# Power_board.net
KiCad netlist of a schematic drawn in Altium Designer
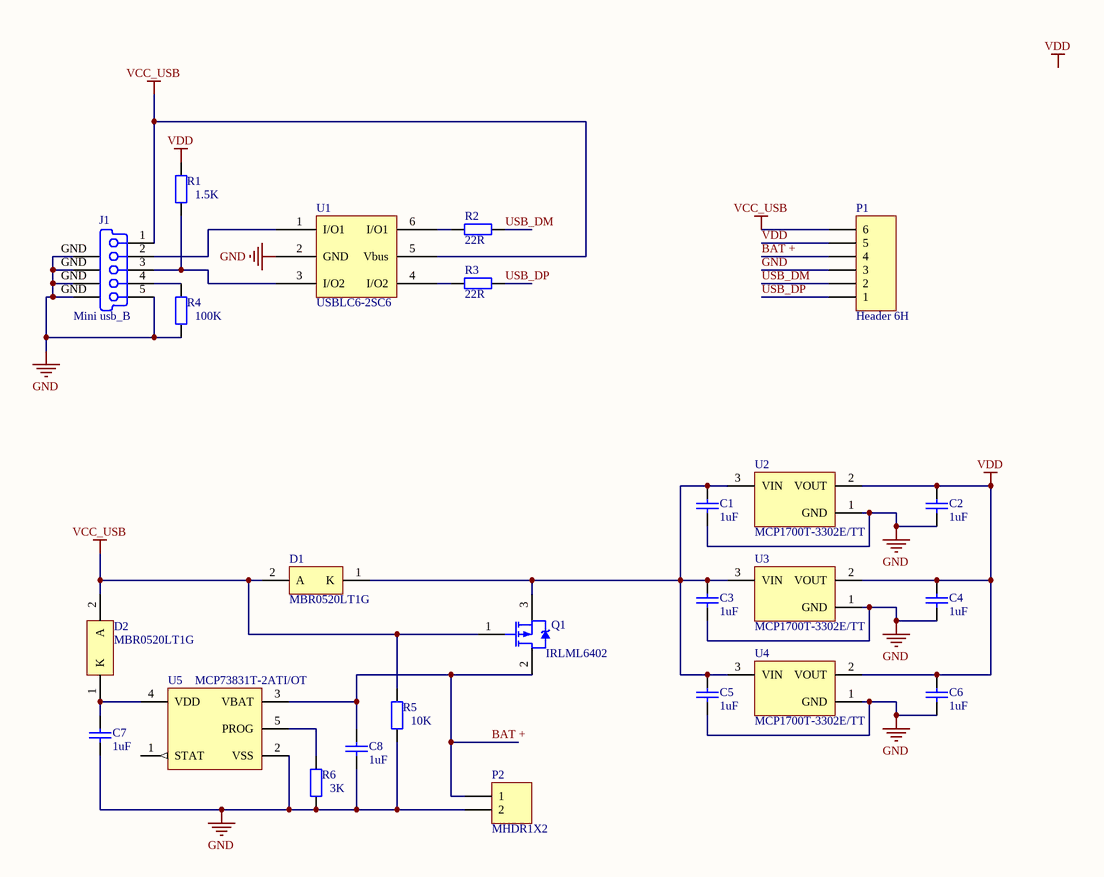
[diagram p0: Power_board.SchDoc]

(export (version "E")
  (design (tool "Eeschema 10.0.6"))
  (components
    (comp (ref "C1")
      (value "1uF")
      (footprint "C0805")
      (description "Capacitor")
      (fields (field (name "PUBLISHER") "Altium Limited"))
      (libsource (lib "Library") (part "Cap"))
    )
    (comp (ref "C2")
      (value "1uF")
      (footprint "C0805")
      (description "Capacitor")
      (fields (field (name "PUBLISHER") "Altium Limited"))
      (libsource (lib "Library") (part "Cap"))
    )
    (comp (ref "C3")
      (value "1uF")
      (footprint "C0805")
      (description "Capacitor")
      (fields (field (name "PUBLISHER") "Altium Limited"))
      (libsource (lib "Library") (part "Cap"))
    )
    (comp (ref "C4")
      (value "1uF")
      (footprint "C0805")
      (description "Capacitor")
      (fields (field (name "PUBLISHER") "Altium Limited"))
      (libsource (lib "Library") (part "Cap"))
    )
    (comp (ref "C5")
      (value "1uF")
      (footprint "C0805")
      (description "Capacitor")
      (fields (field (name "PUBLISHER") "Altium Limited"))
      (libsource (lib "Library") (part "Cap"))
    )
    (comp (ref "C6")
      (value "1uF")
      (footprint "C0805")
      (description "Capacitor")
      (fields (field (name "PUBLISHER") "Altium Limited"))
      (libsource (lib "Library") (part "Cap"))
    )
    (comp (ref "C7")
      (value "1uF")
      (footprint "C0805")
      (description "Capacitor")
      (fields (field (name "PUBLISHER") "Altium Limited"))
      (libsource (lib "Library") (part "Cap"))
    )
    (comp (ref "C8")
      (value "1uF")
      (footprint "C0805")
      (description "Capacitor")
      (fields (field (name "PUBLISHER") "Altium Limited"))
      (libsource (lib "Library") (part "Cap"))
    )
    (comp (ref "D1")
      (value "MBR0520LT1G")
      (footprint "ONSC-SOD-123-2-425-04_V")
      (description "Schottky Power Rectifier, 2-Pin SOD-123, Pb-Free, Tape and Reel")
      (fields (field (name "MANUFACTURER") "On Semiconductor"))
      (libsource (lib "ON Semi Schottky Diodes & Schottky Rectifiers") (part "MBR0520LT1G"))
    )
    (comp (ref "D2")
      (value "MBR0520LT1G")
      (footprint "ONSC-SOD-123-2-425-04_V")
      (description "Schottky Power Rectifier, 2-Pin SOD-123, Pb-Free, Tape and Reel")
      (fields (field (name "MANUFACTURER") "On Semiconductor"))
      (libsource (lib "") (part "MBR0520LT1G_1"))
    )
    (comp (ref "J1")
      (value "Mini usb_B")
      (footprint "Mini_USB_B")
      (fields (field (name "PUBLISHER") "Altium Limited"))
      (libsource (lib "Library") (part "Mini usb_B"))
    )
    (comp (ref "P1")
      (value "Header 6H")
      (footprint "HDR1X6H")
      (description "Header, 6-Pin, Right Angle")
      (fields (field (name "PUBLISHER") "Altium Limited"))
      (libsource (lib "Miscellaneous Connectors") (part "Header 6H"))
    )
    (comp (ref "P2")
      (value "MHDR1X2")
      (footprint "MHDR1X2")
      (description "Header, 2-Pin")
      (fields (field (name "PUBLISHER") "Altium Limited"))
      (libsource (lib "Miscellaneous Connectors") (part "MHDR1X2"))
    )
    (comp (ref "Q1")
      (value "IRLML6402")
      (footprint "SOT95P237X112-3N")
      (libsource (lib "Library") (part "IRLML6402"))
    )
    (comp (ref "R1")
      (value "1.5K")
      (footprint "6-0805_N")
      (description "Resistor")
      (fields (field (name "PUBLISHER") "Altium Limited"))
      (libsource (lib "") (part "Res2_1"))
    )
    (comp (ref "R2")
      (value "22R")
      (footprint "6-0805_N")
      (description "Resistor")
      (fields (field (name "PUBLISHER") "Altium Limited"))
      (libsource (lib "Library") (part "Res2"))
    )
    (comp (ref "R3")
      (value "22R")
      (footprint "6-0805_N")
      (description "Resistor")
      (fields (field (name "PUBLISHER") "Altium Limited"))
      (libsource (lib "Library") (part "Res2"))
    )
    (comp (ref "R4")
      (value "100K")
      (footprint "6-0805_N")
      (description "Resistor")
      (fields (field (name "PUBLISHER") "Altium Limited"))
      (libsource (lib "") (part "Res2_1"))
    )
    (comp (ref "R5")
      (value "10K")
      (footprint "6-0805_N")
      (description "Resistor")
      (fields (field (name "PUBLISHER") "Altium Limited"))
      (libsource (lib "") (part "Res2_1"))
    )
    (comp (ref "R6")
      (value "3K")
      (footprint "6-0805_N")
      (description "Resistor")
      (fields (field (name "PUBLISHER") "Altium Limited"))
      (libsource (lib "") (part "Res2_1"))
    )
    (comp (ref "U1")
      (value "USBLC6-2SC6")
      (footprint "USBLC6-2SC6")
      (libsource (lib "Library") (part "USBLC6-2SC6"))
    )
    (comp (ref "U2")
      (value "MCP1700T-3302E/TT")
      (footprint "SOT-23-TT3_N")
      (description "Low Quiescent Current LDO, 3-Pin SOT-23, Extended Temperature, Tape and Reel")
      (fields (field (name "MANUFACTURER") "Microchip"))
      (libsource (lib "Microchip Power Management Line Regulator") (part "MCP1700T-3302E/TT"))
    )
    (comp (ref "U3")
      (value "MCP1700T-3302E/TT")
      (footprint "SOT-23-TT3_N")
      (description "Low Quiescent Current LDO, 3-Pin SOT-23, Extended Temperature, Tape and Reel")
      (fields (field (name "MANUFACTURER") "Microchip"))
      (libsource (lib "Microchip Power Management Line Regulator") (part "MCP1700T-3302E/TT"))
    )
    (comp (ref "U4")
      (value "MCP1700T-3302E/TT")
      (footprint "SOT-23-TT3_N")
      (description "Low Quiescent Current LDO, 3-Pin SOT-23, Extended Temperature, Tape and Reel")
      (fields (field (name "MANUFACTURER") "Microchip"))
      (libsource (lib "Microchip Power Management Line Regulator") (part "MCP1700T-3302E/TT"))
    )
    (comp (ref "U5")
      (value "MCP73831T-2ATI/OT")
      (footprint "SOT-23-OT5_N")
      (fields (field (name "MANUFACTURER") "Microchip"))
      (libsource (lib "Microchip Power Management Battery Management") (part "MCP73831T-2ATI/OT"))
    )
  )
  (nets
    (net (code "1") (name "/BAT +") (class "Default")
      (node (ref "C8") (pin "2") (pinfunction "2_2") (pintype "passive"))
      (node (ref "P1") (pin "4") (pinfunction "4_4") (pintype "passive"))
      (node (ref "P2") (pin "1") (pinfunction "1_1") (pintype "passive"))
      (node (ref "Q1") (pin "2") (pinfunction "D_2") (pintype "passive"))
      (node (ref "U5") (pin "3") (pinfunction "VBAT_3") (pintype "power_in"))
    )
    (net (code "2") (name "/USB_DM") (class "Default")
      (node (ref "P1") (pin "2") (pinfunction "2_2") (pintype "passive"))
      (node (ref "R2") (pin "2") (pinfunction "2_2") (pintype "passive"))
    )
    (net (code "3") (name "/USB_DP") (class "Default")
      (node (ref "P1") (pin "1") (pinfunction "1_1") (pintype "passive"))
      (node (ref "R3") (pin "2") (pinfunction "2_2") (pintype "passive"))
    )
    (net (code "4") (name "GND") (class "Default")
      (node (ref "C1") (pin "1") (pinfunction "1_1") (pintype "passive"))
      (node (ref "C2") (pin "1") (pinfunction "1_1") (pintype "passive"))
      (node (ref "C3") (pin "1") (pinfunction "1_1") (pintype "passive"))
      (node (ref "C4") (pin "1") (pinfunction "1_1") (pintype "passive"))
      (node (ref "C5") (pin "1") (pinfunction "1_1") (pintype "passive"))
      (node (ref "C6") (pin "1") (pinfunction "1_1") (pintype "passive"))
      (node (ref "C7") (pin "1") (pinfunction "1_1") (pintype "passive"))
      (node (ref "C8") (pin "1") (pinfunction "1_1") (pintype "passive"))
      (node (ref "J1") (pin "5") (pinfunction "GND_5") (pintype "passive"))
      (node (ref "J1") (pin "GND") (pinfunction "Tab_GND") (pintype "passive"))
      (node (ref "P1") (pin "3") (pinfunction "3_3") (pintype "passive"))
      (node (ref "P2") (pin "2") (pinfunction "2_2") (pintype "passive"))
      (node (ref "R4") (pin "1") (pinfunction "1_1") (pintype "passive"))
      (node (ref "R5") (pin "1") (pinfunction "1_1") (pintype "passive"))
      (node (ref "R6") (pin "1") (pinfunction "1_1") (pintype "passive"))
      (node (ref "U1") (pin "2") (pinfunction "GND_2") (pintype "passive"))
      (node (ref "U2") (pin "1") (pinfunction "GND_1") (pintype "power_in"))
      (node (ref "U3") (pin "1") (pinfunction "GND_1") (pintype "power_in"))
      (node (ref "U4") (pin "1") (pinfunction "GND_1") (pintype "power_in"))
      (node (ref "U5") (pin "2") (pinfunction "VSS_2") (pintype "power_in"))
    )
    (net (code "5") (name "Net-(D1-K)") (class "Default")
      (node (ref "C1") (pin "2") (pinfunction "2_2") (pintype "passive"))
      (node (ref "C3") (pin "2") (pinfunction "2_2") (pintype "passive"))
      (node (ref "C5") (pin "2") (pinfunction "2_2") (pintype "passive"))
      (node (ref "D1") (pin "1") (pinfunction "K_1") (pintype "passive"))
      (node (ref "Q1") (pin "3") (pinfunction "S_3") (pintype "passive"))
      (node (ref "U2") (pin "3") (pinfunction "VIN_3") (pintype "power_in"))
      (node (ref "U3") (pin "3") (pinfunction "VIN_3") (pintype "power_in"))
      (node (ref "U4") (pin "3") (pinfunction "VIN_3") (pintype "power_in"))
    )
    (net (code "6") (name "Net-(D2-K)") (class "Default")
      (node (ref "C7") (pin "2") (pinfunction "2_2") (pintype "passive"))
      (node (ref "D2") (pin "1") (pinfunction "K_1") (pintype "passive"))
      (node (ref "U5") (pin "4") (pinfunction "VDD_4") (pintype "power_in"))
    )
    (net (code "7") (name "Net-(J1-D+)") (class "Default")
      (node (ref "J1") (pin "3") (pinfunction "D+_3") (pintype "passive"))
      (node (ref "R1") (pin "1") (pinfunction "1_1") (pintype "passive"))
      (node (ref "U1") (pin "3") (pinfunction "I/O2_3") (pintype "passive"))
    )
    (net (code "8") (name "Net-(J1-D-)") (class "Default")
      (node (ref "J1") (pin "2") (pinfunction "D-_2") (pintype "passive"))
      (node (ref "U1") (pin "1") (pinfunction "I/O1_1") (pintype "passive"))
    )
    (net (code "9") (name "Net-(J1-NC)") (class "Default")
      (node (ref "J1") (pin "4") (pinfunction "NC_4") (pintype "passive"))
      (node (ref "R4") (pin "2") (pinfunction "2_2") (pintype "passive"))
    )
    (net (code "10") (name "Net-(R2-Pad1)") (class "Default")
      (node (ref "R2") (pin "1") (pinfunction "1_1") (pintype "passive"))
      (node (ref "U1") (pin "6") (pinfunction "I/O1_6") (pintype "passive"))
    )
    (net (code "11") (name "Net-(R3-Pad1)") (class "Default")
      (node (ref "R3") (pin "1") (pinfunction "1_1") (pintype "passive"))
      (node (ref "U1") (pin "4") (pinfunction "I/O2_4") (pintype "passive"))
    )
    (net (code "12") (name "Net-(U5-PROG)") (class "Default")
      (node (ref "R6") (pin "2") (pinfunction "2_2") (pintype "passive"))
      (node (ref "U5") (pin "5") (pinfunction "PROG_5") (pintype "passive"))
    )
    (net (code "13") (name "VCC_USB") (class "Default")
      (node (ref "D1") (pin "2") (pinfunction "A_2") (pintype "passive"))
      (node (ref "D2") (pin "2") (pinfunction "A_2") (pintype "passive"))
      (node (ref "J1") (pin "1") (pinfunction "V_BUS_(5V)_1") (pintype "passive"))
      (node (ref "P1") (pin "6") (pinfunction "6_6") (pintype "passive"))
      (node (ref "Q1") (pin "1") (pinfunction "G_1") (pintype "passive"))
      (node (ref "R5") (pin "2") (pinfunction "2_2") (pintype "passive"))
      (node (ref "U1") (pin "5") (pinfunction "Vbus_5") (pintype "passive"))
    )
    (net (code "14") (name "VDD") (class "Default")
      (node (ref "C2") (pin "2") (pinfunction "2_2") (pintype "passive"))
      (node (ref "C4") (pin "2") (pinfunction "2_2") (pintype "passive"))
      (node (ref "C6") (pin "2") (pinfunction "2_2") (pintype "passive"))
      (node (ref "P1") (pin "5") (pinfunction "5_5") (pintype "passive"))
      (node (ref "R1") (pin "2") (pinfunction "2_2") (pintype "passive"))
      (node (ref "U2") (pin "2") (pinfunction "VOUT_2") (pintype "power_in"))
      (node (ref "U3") (pin "2") (pinfunction "VOUT_2") (pintype "power_in"))
      (node (ref "U4") (pin "2") (pinfunction "VOUT_2") (pintype "power_in"))
    )
    (net (code "15") (name "unconnected-(U5-STAT-Pad1)") (class "Default")
      (node (ref "U5") (pin "1") (pinfunction "STAT_1") (pintype "output"))
    )
  )
)
